# 08usb.net
KiCad netlist of a schematic drawn in Altium Designer
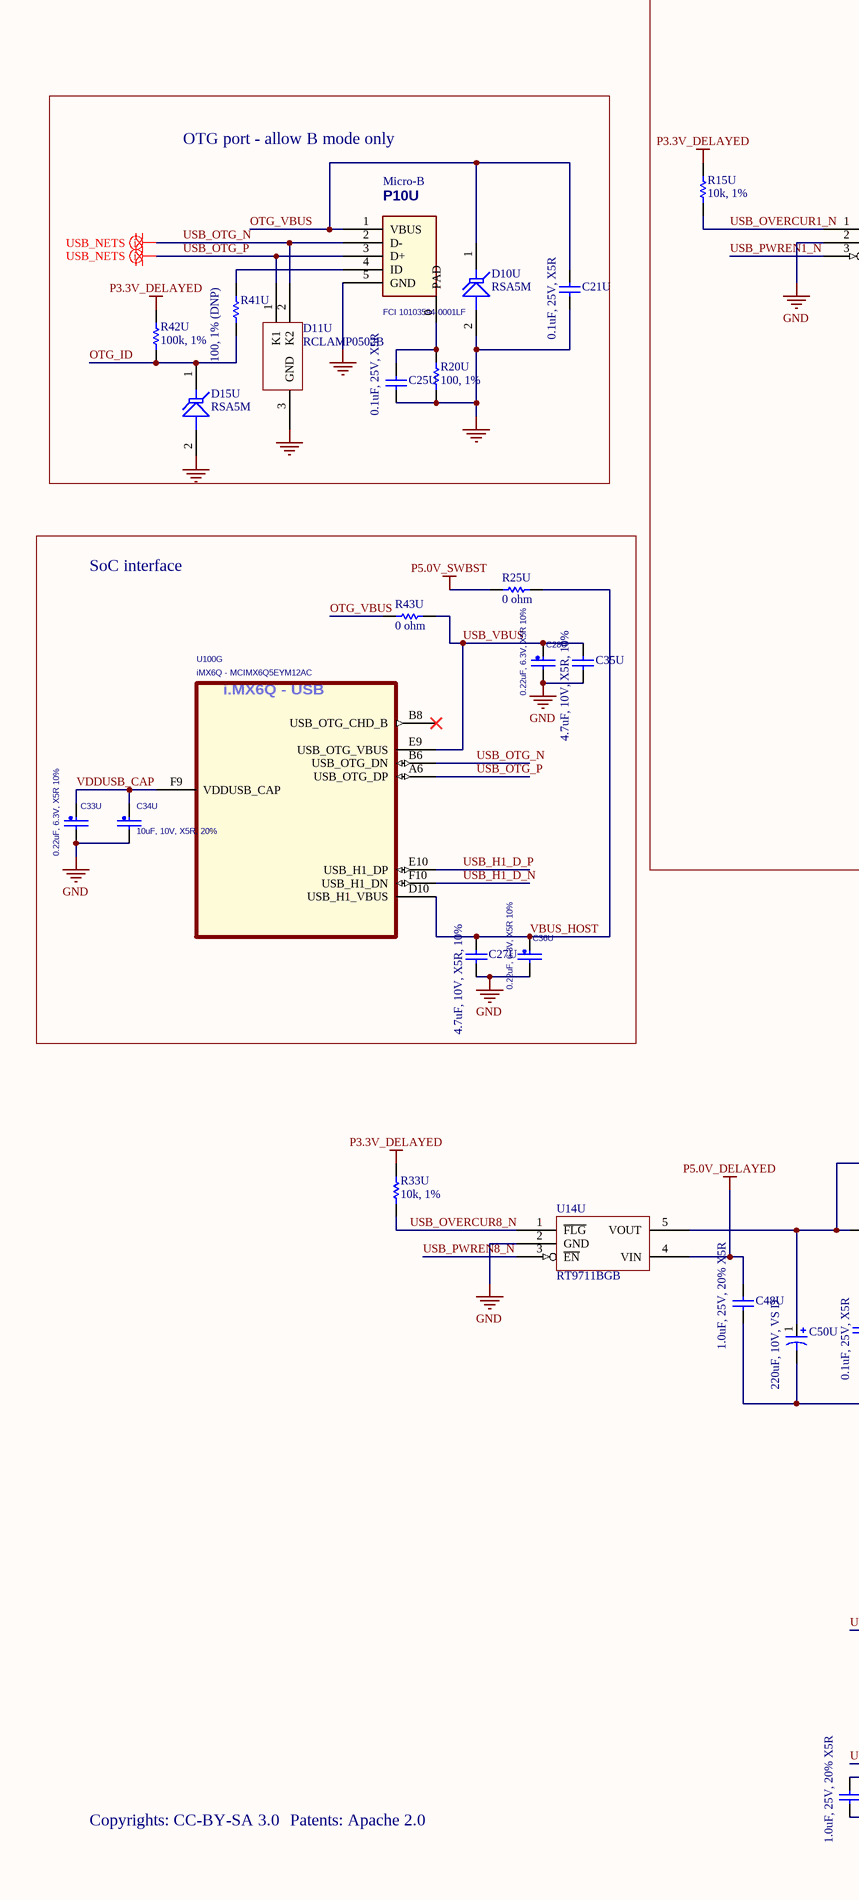
[diagram p0: 08usb.SchDoc, left]
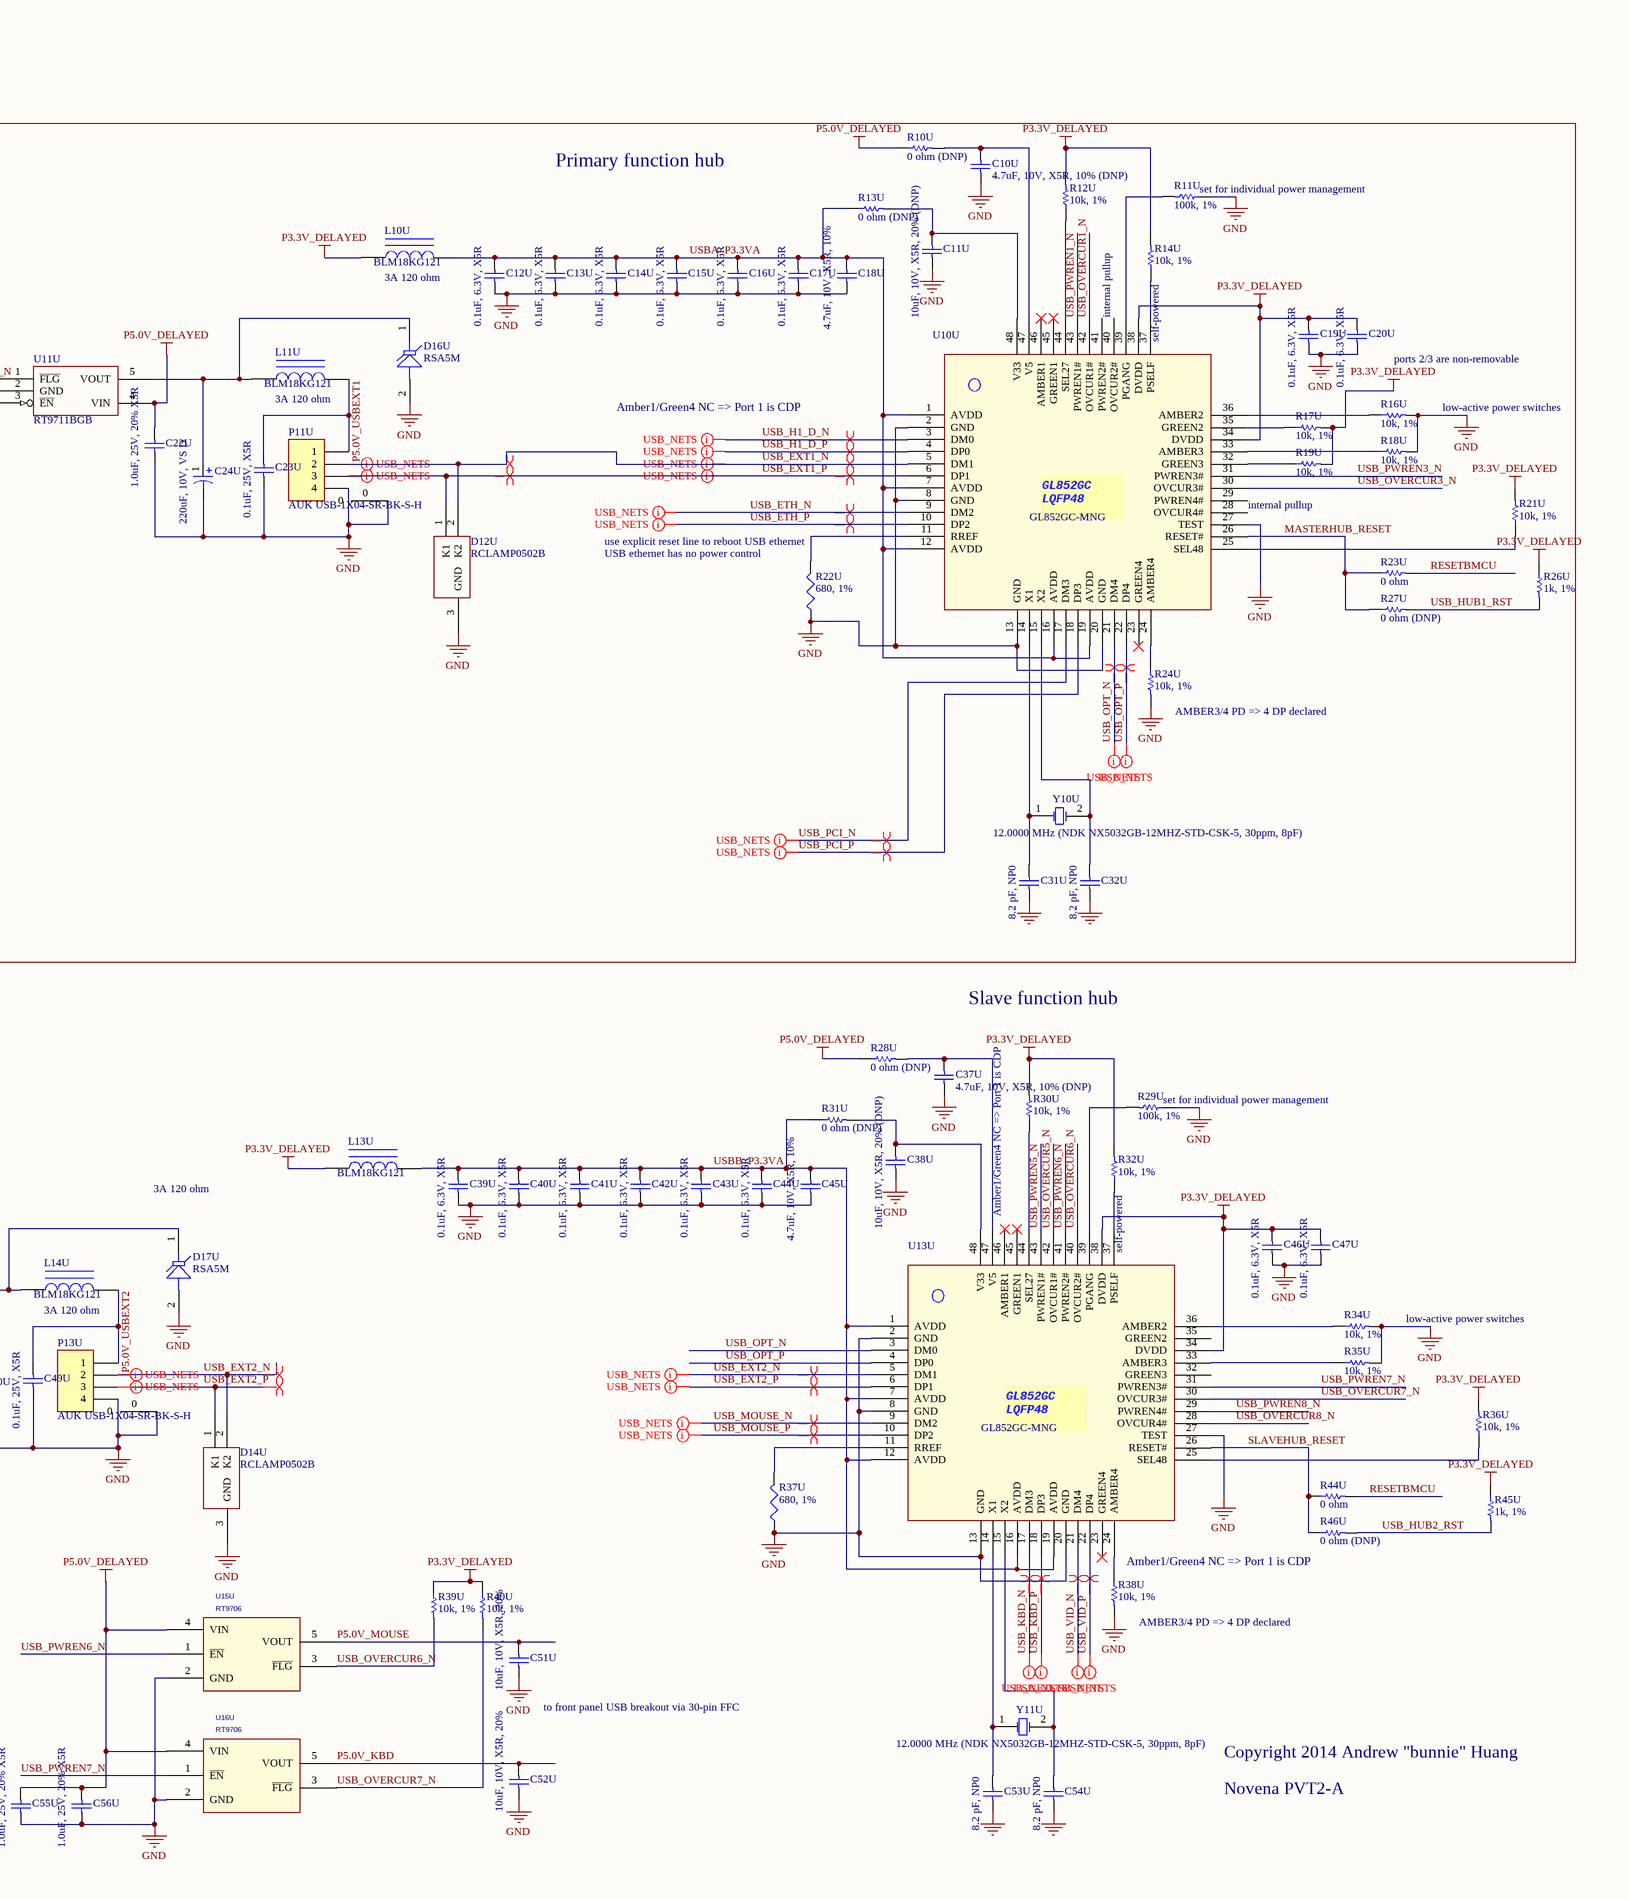
[diagram p1: 08usb.SchDoc, right]

(export (version "E")
  (design (tool "Eeschema 10.0.6"))
  (components
    (comp (ref "C10U")
      (value "4.7uF, 10V, X5R, 10% (DNP)")
      (footprint "CAPC1608N")
      (description "Capacitor (Semiconductor SIM Model)")
      (fields (field (name "PUBLISHER") "Altium Limited"))
      (libsource (lib "Miscellaneous Devices") (part "Cap Semi"))
    )
    (comp (ref "C11U")
      (value "10uF, 10V, X5R, 20% (DNP)")
      (footprint "CAPC1608N")
      (description "Capacitor (Semiconductor SIM Model)")
      (fields (field (name "PUBLISHER") "Altium Limited"))
      (libsource (lib "Miscellaneous Devices") (part "Cap Semi"))
    )
    (comp (ref "C12U")
      (value "0.1uF, 6.3V, X5R")
      (footprint "CAPC0603N_B")
      (description "Capacitor (Semiconductor SIM Model)")
      (fields (field (name "PUBLISHER") "Altium Limited"))
      (libsource (lib "Miscellaneous Devices") (part "Cap Semi"))
    )
    (comp (ref "C13U")
      (value "0.1uF, 6.3V, X5R")
      (footprint "CAPC0603N_B")
      (description "Capacitor (Semiconductor SIM Model)")
      (fields (field (name "PUBLISHER") "Altium Limited"))
      (libsource (lib "Miscellaneous Devices") (part "Cap Semi"))
    )
    (comp (ref "C14U")
      (value "0.1uF, 6.3V, X5R")
      (footprint "CAPC0603N_B")
      (description "Capacitor (Semiconductor SIM Model)")
      (fields (field (name "PUBLISHER") "Altium Limited"))
      (libsource (lib "Miscellaneous Devices") (part "Cap Semi"))
    )
    (comp (ref "C15U")
      (value "0.1uF, 6.3V, X5R")
      (footprint "CAPC0603N_B")
      (description "Capacitor (Semiconductor SIM Model)")
      (fields (field (name "PUBLISHER") "Altium Limited"))
      (libsource (lib "Miscellaneous Devices") (part "Cap Semi"))
    )
    (comp (ref "C16U")
      (value "0.1uF, 6.3V, X5R")
      (footprint "CAPC0603N_B")
      (description "Capacitor (Semiconductor SIM Model)")
      (fields (field (name "PUBLISHER") "Altium Limited"))
      (libsource (lib "Miscellaneous Devices") (part "Cap Semi"))
    )
    (comp (ref "C17U")
      (value "0.1uF, 6.3V, X5R")
      (footprint "CAPC0603N_B")
      (description "Capacitor (Semiconductor SIM Model)")
      (fields (field (name "PUBLISHER") "Altium Limited"))
      (libsource (lib "Miscellaneous Devices") (part "Cap Semi"))
    )
    (comp (ref "C18U")
      (value "4.7uF, 10V, X5R, 10%")
      (footprint "CAPC1608N")
      (description "Capacitor (Semiconductor SIM Model)")
      (fields (field (name "PUBLISHER") "Altium Limited"))
      (libsource (lib "Miscellaneous Devices") (part "Cap Semi"))
    )
    (comp (ref "C19U")
      (value "0.1uF, 6.3V, X5R")
      (footprint "CAPC0603N_B")
      (description "Capacitor (Semiconductor SIM Model)")
      (fields (field (name "PUBLISHER") "Altium Limited"))
      (libsource (lib "Miscellaneous Devices") (part "Cap Semi"))
    )
    (comp (ref "C20U")
      (value "0.1uF, 6.3V, X5R")
      (footprint "CAPC0603N_B")
      (description "Capacitor (Semiconductor SIM Model)")
      (fields (field (name "PUBLISHER") "Altium Limited"))
      (libsource (lib "Miscellaneous Devices") (part "Cap Semi"))
    )
    (comp (ref "C21U")
      (value "0.1uF, 25V, X5R")
      (footprint "CAPC1005N")
      (description "Capacitor (Semiconductor SIM Model)")
      (fields (field (name "PUBLISHER") "Altium Limited"))
      (libsource (lib "Miscellaneous Devices") (part "Cap Semi"))
    )
    (comp (ref "C22U")
      (value "1.0uF, 25V, 20% X5R")
      (footprint "CAPC1608N")
      (description "Capacitor (Semiconductor SIM Model)")
      (fields (field (name "PUBLISHER") "Altium Limited"))
      (libsource (lib "Miscellaneous Devices") (part "Cap Semi"))
    )
    (comp (ref "C23U")
      (value "0.1uF, 25V, X5R")
      (footprint "CAPC1005N")
      (description "Capacitor (Semiconductor SIM Model)")
      (fields (field (name "PUBLISHER") "Altium Limited"))
      (libsource (lib "Miscellaneous Devices") (part "Cap Semi"))
    )
    (comp (ref "C24U")
      (value "220uF, 10V, VS D")
      (footprint "6004pcb:ALCAP_D")
      (description "Polarized Capacitor (Surface Mount)")
      (fields (field (name "PUBLISHER") "Altium Limited"))
      (libsource (lib "Miscellaneous Devices") (part "Cap Pol3"))
    )
    (comp (ref "C25U")
      (value "0.1uF, 25V, X5R")
      (footprint "CAPC1005N")
      (description "Capacitor (Semiconductor SIM Model)")
      (fields (field (name "PUBLISHER") "Altium Limited"))
      (libsource (lib "Miscellaneous Devices") (part "Cap Semi"))
    )
    (comp (ref "C27U")
      (value "4.7uF, 10V, X5R, 10%")
      (footprint "CAPC1608N_HD")
      (description "Capacitor (Semiconductor SIM Model)")
      (fields (field (name "PUBLISHER") "Altium Limited"))
      (libsource (lib "Miscellaneous Devices") (part "Cap Semi"))
    )
    (comp (ref "C28U")
      (value "0.22uF, 6.3V, X5R 10%")
      (footprint "CAPC0603N_B")
      (description "CAP CER 0.22UF 6.3V 20% X5R 0201")
      (fields (field (name "TOLERANCE") "10%"))
      (libsource (lib "*") (part "CAP_NP_Dup1"))
    )
    (comp (ref "C31U")
      (value "8.2 pF, NP0")
      (footprint "CAPC1005N")
      (description "Capacitor (Semiconductor SIM Model)")
      (fields (field (name "PUBLISHER") "Altium Limited"))
      (libsource (lib "Miscellaneous Devices") (part "Cap Semi"))
    )
    (comp (ref "C32U")
      (value "8.2 pF, NP0")
      (footprint "CAPC1005N")
      (description "Capacitor (Semiconductor SIM Model)")
      (fields (field (name "PUBLISHER") "Altium Limited"))
      (libsource (lib "Miscellaneous Devices") (part "Cap Semi"))
    )
    (comp (ref "C33U")
      (value "0.22uF, 6.3V, X5R 10%")
      (footprint "CAPC0603N_B")
      (description "CAP CER 0.22UF 6.3V 20% X5R 0201")
      (fields (field (name "TOLERANCE") "20%"))
      (libsource (lib "*") (part "CAP_NP_Dup1"))
    )
    (comp (ref "C34U")
      (value "10uF, 10V, X5R, 20%")
      (footprint "CAPC1608N_HD")
      (description "CAP CER 10UF 6.3V 10% X5R 0603")
      (fields (field (name "TOLERANCE") "10%"))
      (libsource (lib "*") (part "CAP_NP_Dup1"))
    )
    (comp (ref "C35U")
      (value "4.7uF, 10V, X5R, 10%")
      (footprint "CAPC1608N_HD")
      (description "Capacitor (Semiconductor SIM Model)")
      (fields (field (name "PUBLISHER") "Altium Limited"))
      (libsource (lib "Miscellaneous Devices") (part "Cap Semi"))
    )
    (comp (ref "C36U")
      (value "0.22uF, 6.3V, X5R 10%")
      (footprint "CAPC0603N_B")
      (description "CAP CER 0.22UF 6.3V 20% X5R 0201")
      (fields (field (name "TOLERANCE") "10%"))
      (libsource (lib "*") (part "CAP_NP_Dup1"))
    )
    (comp (ref "C37U")
      (value "4.7uF, 10V, X5R, 10% (DNP)")
      (footprint "CAPC1608N")
      (description "Capacitor (Semiconductor SIM Model)")
      (fields (field (name "PUBLISHER") "Altium Limited"))
      (libsource (lib "Miscellaneous Devices") (part "Cap Semi"))
    )
    (comp (ref "C38U")
      (value "10uF, 10V, X5R, 20% (DNP)")
      (footprint "CAPC1608N")
      (description "Capacitor (Semiconductor SIM Model)")
      (fields (field (name "PUBLISHER") "Altium Limited"))
      (libsource (lib "Miscellaneous Devices") (part "Cap Semi"))
    )
    (comp (ref "C39U")
      (value "0.1uF, 6.3V, X5R")
      (footprint "CAPC0603N_B")
      (description "Capacitor (Semiconductor SIM Model)")
      (fields (field (name "PUBLISHER") "Altium Limited"))
      (libsource (lib "Miscellaneous Devices") (part "Cap Semi"))
    )
    (comp (ref "C40U")
      (value "0.1uF, 6.3V, X5R")
      (footprint "CAPC0603N_B")
      (description "Capacitor (Semiconductor SIM Model)")
      (fields (field (name "PUBLISHER") "Altium Limited"))
      (libsource (lib "Miscellaneous Devices") (part "Cap Semi"))
    )
    (comp (ref "C41U")
      (value "0.1uF, 6.3V, X5R")
      (footprint "CAPC0603N_B")
      (description "Capacitor (Semiconductor SIM Model)")
      (fields (field (name "PUBLISHER") "Altium Limited"))
      (libsource (lib "Miscellaneous Devices") (part "Cap Semi"))
    )
    (comp (ref "C42U")
      (value "0.1uF, 6.3V, X5R")
      (footprint "CAPC0603N_B")
      (description "Capacitor (Semiconductor SIM Model)")
      (fields (field (name "PUBLISHER") "Altium Limited"))
      (libsource (lib "Miscellaneous Devices") (part "Cap Semi"))
    )
    (comp (ref "C43U")
      (value "0.1uF, 6.3V, X5R")
      (footprint "CAPC0603N_B")
      (description "Capacitor (Semiconductor SIM Model)")
      (fields (field (name "PUBLISHER") "Altium Limited"))
      (libsource (lib "Miscellaneous Devices") (part "Cap Semi"))
    )
    (comp (ref "C44U")
      (value "0.1uF, 6.3V, X5R")
      (footprint "CAPC0603N_B")
      (description "Capacitor (Semiconductor SIM Model)")
      (fields (field (name "PUBLISHER") "Altium Limited"))
      (libsource (lib "Miscellaneous Devices") (part "Cap Semi"))
    )
    (comp (ref "C45U")
      (value "4.7uF, 10V, X5R, 10%")
      (footprint "CAPC1608N")
      (description "Capacitor (Semiconductor SIM Model)")
      (fields (field (name "PUBLISHER") "Altium Limited"))
      (libsource (lib "Miscellaneous Devices") (part "Cap Semi"))
    )
    (comp (ref "C46U")
      (value "0.1uF, 6.3V, X5R")
      (footprint "CAPC0603N_B")
      (description "Capacitor (Semiconductor SIM Model)")
      (fields (field (name "PUBLISHER") "Altium Limited"))
      (libsource (lib "Miscellaneous Devices") (part "Cap Semi"))
    )
    (comp (ref "C47U")
      (value "0.1uF, 6.3V, X5R")
      (footprint "CAPC0603N_B")
      (description "Capacitor (Semiconductor SIM Model)")
      (fields (field (name "PUBLISHER") "Altium Limited"))
      (libsource (lib "Miscellaneous Devices") (part "Cap Semi"))
    )
    (comp (ref "C48U")
      (value "1.0uF, 25V, 20% X5R")
      (footprint "CAPC1608N")
      (description "Capacitor (Semiconductor SIM Model)")
      (fields (field (name "PUBLISHER") "Altium Limited"))
      (libsource (lib "Miscellaneous Devices") (part "Cap Semi"))
    )
    (comp (ref "C49U")
      (value "0.1uF, 25V, X5R")
      (footprint "CAPC1005N")
      (description "Capacitor (Semiconductor SIM Model)")
      (fields (field (name "PUBLISHER") "Altium Limited"))
      (libsource (lib "Miscellaneous Devices") (part "Cap Semi"))
    )
    (comp (ref "C50U")
      (value "220uF, 10V, VS D")
      (footprint "6004pcb:ALCAP_D")
      (description "Polarized Capacitor (Surface Mount)")
      (fields (field (name "PUBLISHER") "Altium Limited"))
      (libsource (lib "Miscellaneous Devices") (part "Cap Pol3"))
    )
    (comp (ref "C51U")
      (value "10uF, 10V, X5R, 20%")
      (footprint "CAPC1608N")
      (description "Capacitor (Semiconductor SIM Model)")
      (fields (field (name "PUBLISHER") "Altium Limited"))
      (libsource (lib "Miscellaneous Devices") (part "Cap Semi"))
    )
    (comp (ref "C52U")
      (value "10uF, 10V, X5R, 20%")
      (footprint "CAPC1608N")
      (description "Capacitor (Semiconductor SIM Model)")
      (fields (field (name "PUBLISHER") "Altium Limited"))
      (libsource (lib "Miscellaneous Devices") (part "Cap Semi"))
    )
    (comp (ref "C53U")
      (value "8.2 pF, NP0")
      (footprint "CAPC1005N")
      (description "Capacitor (Semiconductor SIM Model)")
      (fields (field (name "PUBLISHER") "Altium Limited"))
      (libsource (lib "Miscellaneous Devices") (part "Cap Semi"))
    )
    (comp (ref "C54U")
      (value "8.2 pF, NP0")
      (footprint "CAPC1005N")
      (description "Capacitor (Semiconductor SIM Model)")
      (fields (field (name "PUBLISHER") "Altium Limited"))
      (libsource (lib "Miscellaneous Devices") (part "Cap Semi"))
    )
    (comp (ref "C55U")
      (value "1.0uF, 25V, 20% X5R")
      (footprint "CAPC1608N")
      (description "Capacitor (Semiconductor SIM Model)")
      (fields (field (name "PUBLISHER") "Altium Limited"))
      (libsource (lib "Miscellaneous Devices") (part "Cap Semi"))
    )
    (comp (ref "C56U")
      (value "1.0uF, 25V, 20% X5R")
      (footprint "CAPC1608N")
      (description "Capacitor (Semiconductor SIM Model)")
      (fields (field (name "PUBLISHER") "Altium Limited"))
      (libsource (lib "Miscellaneous Devices") (part "Cap Semi"))
    )
    (comp (ref "D10U")
      (value "RSA5M")
      (footprint "SOD123/X.85")
      (description "Tranzorb")
      (fields (field (name "PUBLISHER") "Altium Limited"))
      (libsource (lib "Miscellaneous Devices") (part "Tranzorb"))
    )
    (comp (ref "D11U")
      (value "RCLAMP0502B")
      (footprint "SOT-523")
      (description "2-channel ESD/CDE protection device for 5V devices")
      (libsource (lib "*") (part "RCLAMP0502B"))
    )
    (comp (ref "D12U")
      (value "RCLAMP0502B")
      (footprint "SOT-523")
      (description "2-channel ESD/CDE protection device for 5V devices")
      (libsource (lib "*") (part "RCLAMP0502B"))
    )
    (comp (ref "D14U")
      (value "RCLAMP0502B")
      (footprint "SOT-523")
      (description "2-channel ESD/CDE protection device for 5V devices")
      (libsource (lib "*") (part "RCLAMP0502B"))
    )
    (comp (ref "D15U")
      (value "RSA5M")
      (footprint "SOD123/X.85")
      (description "Tranzorb")
      (fields (field (name "PUBLISHER") "Altium Limited"))
      (libsource (lib "Miscellaneous Devices") (part "Tranzorb"))
    )
    (comp (ref "D16U")
      (value "RSA5M")
      (footprint "SOD123/X.85")
      (description "Tranzorb")
      (fields (field (name "PUBLISHER") "Altium Limited"))
      (libsource (lib "Miscellaneous Devices") (part "Tranzorb"))
    )
    (comp (ref "D17U")
      (value "RSA5M")
      (footprint "SOD123/X.85")
      (description "Tranzorb")
      (fields (field (name "PUBLISHER") "Altium Limited"))
      (libsource (lib "Miscellaneous Devices") (part "Tranzorb"))
    )
    (comp (ref "L10U")
      (value "BLM18KG121")
      (footprint "INDC1608AN")
      (description "Magnetic-Core Inductor")
      (fields (field (name "ALTIUM_VALUE") "3A 120 ohm") (field (name "PUBLISHER") "Altium Limited"))
      (libsource (lib "Miscellaneous Devices") (part "Inductor Iron"))
    )
    (comp (ref "L11U")
      (value "BLM18KG121")
      (footprint "INDC1608AN")
      (description "Magnetic-Core Inductor")
      (fields (field (name "ALTIUM_VALUE") "3A 120 ohm") (field (name "PUBLISHER") "Altium Limited"))
      (libsource (lib "Miscellaneous Devices") (part "Inductor Iron"))
    )
    (comp (ref "L13U")
      (value "BLM18KG121")
      (footprint "INDC1608AN")
      (description "Magnetic-Core Inductor")
      (fields (field (name "ALTIUM_VALUE") "3A 120 ohm") (field (name "PUBLISHER") "Altium Limited"))
      (libsource (lib "Miscellaneous Devices") (part "Inductor Iron"))
    )
    (comp (ref "L14U")
      (value "BLM18KG121")
      (footprint "INDC1608AN")
      (description "Magnetic-Core Inductor")
      (fields (field (name "ALTIUM_VALUE") "3A 120 ohm") (field (name "PUBLISHER") "Altium Limited"))
      (libsource (lib "Miscellaneous Devices") (part "Inductor Iron"))
    )
    (comp (ref "P10U")
      (value "FCI 10103594-0001LF")
      (footprint "USB_MICRO_B_SMT")
      (description "Micro USB B type connector, i.e. FCI 10103594")
      (libsource (lib "*") (part "USB_MINI-AB_1"))
    )
    (comp (ref "P11U")
      (value "AUK USB-1X04-SR-BK-S-H")
      (footprint "USB_TYPEA_TH_SINGLE")
      (description "Header, 4-Pin")
      (fields (field (name "PUBLISHER") "Altium Limited"))
      (libsource (lib "Miscellaneous Connectors") (part "Header 4"))
    )
    (comp (ref "P13U")
      (value "AUK USB-1X04-SR-BK-S-H")
      (footprint "USB_TYPEA_TH_SINGLE")
      (description "Header, 4-Pin")
      (fields (field (name "PUBLISHER") "Altium Limited"))
      (libsource (lib "Miscellaneous Connectors") (part "Header 4"))
    )
    (comp (ref "R10U")
      (value "0 ohm (DNP)")
      (footprint "RESC1005N")
      (description "Resistor")
      (fields (field (name "PUBLISHER") "Altium Limited"))
      (libsource (lib "Miscellaneous Devices") (part "Res1"))
    )
    (comp (ref "R11U")
      (value "100k, 1%")
      (footprint "RESC1005N")
      (description "Resistor")
      (fields (field (name "PUBLISHER") "Altium Limited"))
      (libsource (lib "Miscellaneous Devices") (part "Res1"))
    )
    (comp (ref "R12U")
      (value "10k, 1%")
      (footprint "RESC1005N")
      (description "Resistor")
      (fields (field (name "PUBLISHER") "Altium Limited"))
      (libsource (lib "Miscellaneous Devices") (part "Res1"))
    )
    (comp (ref "R13U")
      (value "0 ohm (DNP)")
      (footprint "RESC1005N")
      (description "Resistor")
      (fields (field (name "PUBLISHER") "Altium Limited"))
      (libsource (lib "Miscellaneous Devices") (part "Res1"))
    )
    (comp (ref "R14U")
      (value "10k, 1%")
      (footprint "RESC1005N")
      (description "Resistor")
      (fields (field (name "PUBLISHER") "Altium Limited"))
      (libsource (lib "Miscellaneous Devices") (part "Res1"))
    )
    (comp (ref "R15U")
      (value "10k, 1%")
      (footprint "RESC1005N")
      (description "Resistor")
      (fields (field (name "PUBLISHER") "Altium Limited"))
      (libsource (lib "Miscellaneous Devices") (part "Res1"))
    )
    (comp (ref "R16U")
      (value "10k, 1%")
      (footprint "RESC1005N")
      (description "Resistor")
      (fields (field (name "PUBLISHER") "Altium Limited"))
      (libsource (lib "Miscellaneous Devices") (part "Res1"))
    )
    (comp (ref "R17U")
      (value "10k, 1%")
      (footprint "RESC1005N")
      (description "Resistor")
      (fields (field (name "PUBLISHER") "Altium Limited"))
      (libsource (lib "Miscellaneous Devices") (part "Res1"))
    )
    (comp (ref "R18U")
      (value "10k, 1%")
      (footprint "RESC1005N")
      (description "Resistor")
      (fields (field (name "PUBLISHER") "Altium Limited"))
      (libsource (lib "Miscellaneous Devices") (part "Res1"))
    )
    (comp (ref "R19U")
      (value "10k, 1%")
      (footprint "RESC1005N")
      (description "Resistor")
      (fields (field (name "PUBLISHER") "Altium Limited"))
      (libsource (lib "Miscellaneous Devices") (part "Res1"))
    )
    (comp (ref "R20U")
      (value "100, 1%")
      (footprint "RESC1005N")
      (description "Resistor")
      (fields (field (name "PUBLISHER") "Altium Limited"))
      (libsource (lib "Miscellaneous Devices") (part "Res1"))
    )
    (comp (ref "R21U")
      (value "10k, 1%")
      (footprint "RESC1005N")
      (description "Resistor")
      (fields (field (name "PUBLISHER") "Altium Limited"))
      (libsource (lib "Miscellaneous Devices") (part "Res1"))
    )
    (comp (ref "R22U")
      (value "680, 1%")
      (footprint "RESC1005N")
      (description "Resistor")
      (fields (field (name "PUBLISHER") "Altium Limited"))
      (libsource (lib "Miscellaneous Devices") (part "Res3"))
    )
    (comp (ref "R23U")
      (value "0 ohm")
      (footprint "RESC1005N")
      (description "Resistor")
      (fields (field (name "PUBLISHER") "Altium Limited"))
      (libsource (lib "Miscellaneous Devices") (part "Res1"))
    )
    (comp (ref "R24U")
      (value "10k, 1%")
      (footprint "RESC1005N")
      (description "Resistor")
      (fields (field (name "PUBLISHER") "Altium Limited"))
      (libsource (lib "Miscellaneous Devices") (part "Res1"))
    )
    (comp (ref "R25U")
      (value "0 ohm")
      (footprint "RESC1005N")
      (description "Resistor")
      (fields (field (name "PUBLISHER") "Altium Limited"))
      (libsource (lib "Miscellaneous Devices") (part "Res1"))
    )
    (comp (ref "R26U")
      (value "1k, 1%")
      (footprint "RESC1005N")
      (description "Resistor")
      (fields (field (name "PUBLISHER") "Altium Limited"))
      (libsource (lib "Miscellaneous Devices") (part "Res1"))
    )
    (comp (ref "R27U")
      (value "0 ohm (DNP)")
      (footprint "RESC1005N")
      (description "Resistor")
      (fields (field (name "PUBLISHER") "Altium Limited"))
      (libsource (lib "Miscellaneous Devices") (part "Res1"))
    )
    (comp (ref "R28U")
      (value "0 ohm (DNP)")
      (footprint "RESC1005N")
      (description "Resistor")
      (fields (field (name "PUBLISHER") "Altium Limited"))
      (libsource (lib "Miscellaneous Devices") (part "Res1"))
    )
    (comp (ref "R29U")
      (value "100k, 1%")
      (footprint "RESC1005N")
      (description "Resistor")
      (fields (field (name "PUBLISHER") "Altium Limited"))
      (libsource (lib "Miscellaneous Devices") (part "Res1"))
    )
    (comp (ref "R30U")
      (value "10k, 1%")
      (footprint "RESC1005N")
      (description "Resistor")
      (fields (field (name "PUBLISHER") "Altium Limited"))
      (libsource (lib "Miscellaneous Devices") (part "Res1"))
    )
    (comp (ref "R31U")
      (value "0 ohm (DNP)")
      (footprint "RESC1005N")
      (description "Resistor")
      (fields (field (name "PUBLISHER") "Altium Limited"))
      (libsource (lib "Miscellaneous Devices") (part "Res1"))
    )
    (comp (ref "R32U")
      (value "10k, 1%")
      (footprint "RESC1005N")
      (description "Resistor")
      (fields (field (name "PUBLISHER") "Altium Limited"))
      (libsource (lib "Miscellaneous Devices") (part "Res1"))
    )
    (comp (ref "R33U")
      (value "10k, 1%")
      (footprint "RESC1005N")
      (description "Resistor")
      (fields (field (name "PUBLISHER") "Altium Limited"))
      (libsource (lib "Miscellaneous Devices") (part "Res1"))
    )
    (comp (ref "R34U")
      (value "10k, 1%")
      (footprint "RESC1005N")
      (description "Resistor")
      (fields (field (name "PUBLISHER") "Altium Limited"))
      (libsource (lib "Miscellaneous Devices") (part "Res1"))
    )
    (comp (ref "R35U")
      (value "10k, 1%")
      (footprint "RESC1005N")
      (description "Resistor")
      (fields (field (name "PUBLISHER") "Altium Limited"))
      (libsource (lib "Miscellaneous Devices") (part "Res1"))
    )
    (comp (ref "R36U")
      (value "10k, 1%")
      (footprint "RESC1005N")
      (description "Resistor")
      (fields (field (name "PUBLISHER") "Altium Limited"))
      (libsource (lib "Miscellaneous Devices") (part "Res1"))
    )
    (comp (ref "R37U")
      (value "680, 1%")
      (footprint "RESC1005N")
      (description "Resistor")
      (fields (field (name "PUBLISHER") "Altium Limited"))
      (libsource (lib "Miscellaneous Devices") (part "Res3"))
    )
    (comp (ref "R38U")
      (value "10k, 1%")
      (footprint "RESC1005N")
      (description "Resistor")
      (fields (field (name "PUBLISHER") "Altium Limited"))
      (libsource (lib "Miscellaneous Devices") (part "Res1"))
    )
    (comp (ref "R39U")
      (value "10k, 1%")
      (footprint "RESC1005N")
      (description "Resistor")
      (fields (field (name "PUBLISHER") "Altium Limited"))
      (libsource (lib "Miscellaneous Devices") (part "Res1"))
    )
    (comp (ref "R40U")
      (value "10k, 1%")
      (footprint "RESC1005N")
      (description "Resistor")
      (fields (field (name "PUBLISHER") "Altium Limited"))
      (libsource (lib "Miscellaneous Devices") (part "Res1"))
    )
    (comp (ref "R41U")
      (value "100, 1% (DNP)")
      (footprint "RESC1005N")
      (description "Resistor")
      (fields (field (name "PUBLISHER") "Altium Limited"))
      (libsource (lib "Miscellaneous Devices") (part "Res1"))
    )
    (comp (ref "R42U")
      (value "100k, 1%")
      (footprint "RESC1005N")
      (description "Resistor")
      (fields (field (name "PUBLISHER") "Altium Limited"))
      (libsource (lib "Miscellaneous Devices") (part "Res1"))
    )
    (comp (ref "R43U")
      (value "0 ohm")
      (footprint "RESC1005N")
      (description "Resistor")
      (fields (field (name "PUBLISHER") "Altium Limited"))
      (libsource (lib "Miscellaneous Devices") (part "Res1"))
    )
    (comp (ref "R44U")
      (value "0 ohm")
      (footprint "RESC1005N")
      (description "Resistor")
      (fields (field (name "PUBLISHER") "Altium Limited"))
      (libsource (lib "Miscellaneous Devices") (part "Res1"))
    )
    (comp (ref "R45U")
      (value "1k, 1%")
      (footprint "RESC1005N")
      (description "Resistor")
      (fields (field (name "PUBLISHER") "Altium Limited"))
      (libsource (lib "Miscellaneous Devices") (part "Res1"))
    )
    (comp (ref "R46U")
      (value "0 ohm (DNP)")
      (footprint "RESC1005N")
      (description "Resistor")
      (fields (field (name "PUBLISHER") "Altium Limited"))
      (libsource (lib "Miscellaneous Devices") (part "Res1"))
    )
    (comp (ref "U10U")
      (value "GL852GC-MNG")
      (description "4-port multiple-TT hub with USB charging support")
      (libsource (lib "*") (part "GLI8024-48_4"))
    )
    (comp (ref "U11U")
      (value "RT9711BGB")
      (footprint "SOT23-5AN")
      (description "1.5A high-side power switch, active low enable")
      (libsource (lib "commonsch") (part "RT9711BGB"))
    )
    (comp (ref "U13U")
      (value "GL852GC-MNG")
      (description "4-port multiple-TT hub with USB charging support")
      (libsource (lib "*") (part "GLI8024-48_4"))
    )
    (comp (ref "U14U")
      (value "RT9711BGB")
      (footprint "SOT23-5AN")
      (description "1.5A high-side power switch, active low enable")
      (libsource (lib "commonsch") (part "RT9711BGB"))
    )
    (comp (ref "U15U")
      (value "RT9706")
      (description "IC LIN SW W/FLAG 500MA 2.0-5.5V SOT23-5")
      (libsource (lib "*") (part "RT9706"))
    )
    (comp (ref "U16U")
      (value "RT9706")
      (description "IC LIN SW W/FLAG 500MA 2.0-5.5V SOT23-5")
      (libsource (lib "*") (part "RT9706"))
    )
    (comp (ref "U100")
      (value "iMX6Q - MCIMX6Q5EYM12AC")
      (description "PCIMX6Q5EVT10AC")
      (libsource (lib "*") (part "PCIMX6Q6VV1A"))
    )
    (comp (ref "Y10U")
      (value "12.0000 MHz (NDK NX5032GB-12MHZ-STD-CSK-5, 30ppm, 8pF)")
      (footprint "NDK_NX5032A")
      (description "Crystal Oscillator")
      (fields (field (name "PUBLISHER") "Altium Limited"))
      (libsource (lib "Miscellaneous Devices") (part "XTAL"))
    )
    (comp (ref "Y11U")
      (value "12.0000 MHz (NDK NX5032GB-12MHZ-STD-CSK-5, 30ppm, 8pF)")
      (footprint "NDK_NX5032A")
      (description "Crystal Oscillator")
      (fields (field (name "PUBLISHER") "Altium Limited"))
      (libsource (lib "Miscellaneous Devices") (part "XTAL"))
    )
  )
  (nets
    (net (code "1") (name "/MASTERHUB_RESET") (class "Default")
      (node (ref "R23U") (pin "1") (pinfunction "1_1") (pintype "passive"))
      (node (ref "R27U") (pin "1") (pinfunction "1_1") (pintype "passive"))
      (node (ref "U10U") (pin "26") (pinfunction "RESET#_26") (pintype "passive"))
    )
    (net (code "2") (name "/OTG_ID") (class "Default")
      (node (ref "D15U") (pin "1") (pinfunction "K_1") (pintype "passive"))
      (node (ref "R41U") (pin "1") (pinfunction "1_1") (pintype "passive"))
      (node (ref "R42U") (pin "1") (pinfunction "1_1") (pintype "passive"))
    )
    (net (code "3") (name "/OTG_VBUS") (class "Default")
      (node (ref "C21U") (pin "1") (pinfunction "1_1") (pintype "passive"))
      (node (ref "D10U") (pin "1") (pinfunction "K_1") (pintype "passive"))
      (node (ref "P10U") (pin "1") (pinfunction "VBUS_1") (pintype "passive"))
      (node (ref "R43U") (pin "2") (pinfunction "2_2") (pintype "passive"))
    )
    (net (code "4") (name "/P5.0V_KBD") (class "Default")
      (node (ref "C52U") (pin "1") (pinfunction "1_1") (pintype "passive"))
      (node (ref "U16U") (pin "5") (pinfunction "VOUT_5") (pintype "passive"))
    )
    (net (code "5") (name "/P5.0V_MOUSE") (class "Default")
      (node (ref "C51U") (pin "1") (pinfunction "1_1") (pintype "passive"))
      (node (ref "U15U") (pin "5") (pinfunction "VOUT_5") (pintype "passive"))
    )
    (net (code "6") (name "/P5.0V_USBEXT1") (class "Default")
      (node (ref "C23U") (pin "1") (pinfunction "1_1") (pintype "passive"))
      (node (ref "L11U") (pin "2") (pinfunction "2_2") (pintype "passive"))
      (node (ref "P11U") (pin "1") (pinfunction "1_1") (pintype "passive"))
    )
    (net (code "7") (name "/P5.0V_USBEXT2") (class "Default")
      (node (ref "C49U") (pin "1") (pinfunction "1_1") (pintype "passive"))
      (node (ref "L14U") (pin "2") (pinfunction "2_2") (pintype "passive"))
      (node (ref "P13U") (pin "1") (pinfunction "1_1") (pintype "passive"))
    )
    (net (code "8") (name "/RESETBMCU") (class "Default")
      (node (ref "R23U") (pin "2") (pinfunction "2_2") (pintype "passive"))
      (node (ref "R44U") (pin "2") (pinfunction "2_2") (pintype "passive"))
    )
    (net (code "9") (name "/SLAVEHUB_RESET") (class "Default")
      (node (ref "R44U") (pin "1") (pinfunction "1_1") (pintype "passive"))
      (node (ref "R46U") (pin "1") (pinfunction "1_1") (pintype "passive"))
      (node (ref "U13U") (pin "26") (pinfunction "RESET#_26") (pintype "passive"))
    )
    (net (code "10") (name "/USBA_P3.3VA") (class "Default")
      (node (ref "C12U") (pin "1") (pinfunction "1_1") (pintype "passive"))
      (node (ref "C13U") (pin "1") (pinfunction "1_1") (pintype "passive"))
      (node (ref "C14U") (pin "1") (pinfunction "1_1") (pintype "passive"))
      (node (ref "C15U") (pin "1") (pinfunction "1_1") (pintype "passive"))
      (node (ref "C16U") (pin "1") (pinfunction "1_1") (pintype "passive"))
      (node (ref "C17U") (pin "1") (pinfunction "1_1") (pintype "passive"))
      (node (ref "C18U") (pin "1") (pinfunction "1_1") (pintype "passive"))
      (node (ref "L10U") (pin "2") (pinfunction "2_2") (pintype "passive"))
      (node (ref "R13U") (pin "1") (pinfunction "1_1") (pintype "passive"))
      (node (ref "U10U") (pin "1") (pinfunction "AVDD_1") (pintype "passive"))
      (node (ref "U10U") (pin "12") (pinfunction "AVDD_12") (pintype "passive"))
      (node (ref "U10U") (pin "16") (pinfunction "AVDD_16") (pintype "passive"))
      (node (ref "U10U") (pin "19") (pinfunction "AVDD_19") (pintype "passive"))
      (node (ref "U10U") (pin "7") (pinfunction "AVDD_7") (pintype "passive"))
    )
    (net (code "11") (name "/USBB_P3.3VA") (class "Default")
      (node (ref "C39U") (pin "1") (pinfunction "1_1") (pintype "passive"))
      (node (ref "C40U") (pin "1") (pinfunction "1_1") (pintype "passive"))
      (node (ref "C41U") (pin "1") (pinfunction "1_1") (pintype "passive"))
      (node (ref "C42U") (pin "1") (pinfunction "1_1") (pintype "passive"))
      (node (ref "C43U") (pin "1") (pinfunction "1_1") (pintype "passive"))
      (node (ref "C44U") (pin "1") (pinfunction "1_1") (pintype "passive"))
      (node (ref "C45U") (pin "1") (pinfunction "1_1") (pintype "passive"))
      (node (ref "L13U") (pin "2") (pinfunction "2_2") (pintype "passive"))
      (node (ref "R31U") (pin "1") (pinfunction "1_1") (pintype "passive"))
      (node (ref "U13U") (pin "1") (pinfunction "AVDD_1") (pintype "passive"))
      (node (ref "U13U") (pin "12") (pinfunction "AVDD_12") (pintype "passive"))
      (node (ref "U13U") (pin "16") (pinfunction "AVDD_16") (pintype "passive"))
      (node (ref "U13U") (pin "19") (pinfunction "AVDD_19") (pintype "passive"))
      (node (ref "U13U") (pin "7") (pinfunction "AVDD_7") (pintype "passive"))
    )
    (net (code "12") (name "/USB_ETH_N") (class "Default")
      (node (ref "U10U") (pin "9") (pinfunction "DM2_9") (pintype "passive"))
    )
    (net (code "13") (name "/USB_ETH_P") (class "Default")
      (node (ref "U10U") (pin "10") (pinfunction "DP2_10") (pintype "passive"))
    )
    (net (code "14") (name "/USB_EXT1_N") (class "Default")
      (node (ref "D12U") (pin "2") (pinfunction "K2_2") (pintype "passive"))
      (node (ref "P11U") (pin "2") (pinfunction "2_2") (pintype "passive"))
      (node (ref "U10U") (pin "5") (pinfunction "DM1_5") (pintype "passive"))
    )
    (net (code "15") (name "/USB_EXT1_P") (class "Default")
      (node (ref "D12U") (pin "1") (pinfunction "K1_1") (pintype "passive"))
      (node (ref "P11U") (pin "3") (pinfunction "3_3") (pintype "passive"))
      (node (ref "U10U") (pin "6") (pinfunction "DP1_6") (pintype "passive"))
    )
    (net (code "16") (name "/USB_EXT2_N") (class "Default")
      (node (ref "D14U") (pin "2") (pinfunction "K2_2") (pintype "passive"))
      (node (ref "P13U") (pin "2") (pinfunction "2_2") (pintype "passive"))
      (node (ref "U13U") (pin "5") (pinfunction "DM1_5") (pintype "passive"))
    )
    (net (code "17") (name "/USB_EXT2_P") (class "Default")
      (node (ref "D14U") (pin "1") (pinfunction "K1_1") (pintype "passive"))
      (node (ref "P13U") (pin "3") (pinfunction "3_3") (pintype "passive"))
      (node (ref "U13U") (pin "6") (pinfunction "DP1_6") (pintype "passive"))
    )
    (net (code "18") (name "/USB_H1_D_N") (class "Default")
      (node (ref "U100") (pin "F10") (pinfunction "USB_H1_DN_F10") (pintype "bidirectional"))
      (node (ref "U10U") (pin "3") (pinfunction "DM0_3") (pintype "passive"))
    )
    (net (code "19") (name "/USB_H1_D_P") (class "Default")
      (node (ref "U100") (pin "E10") (pinfunction "USB_H1_DP_E10") (pintype "bidirectional"))
      (node (ref "U10U") (pin "4") (pinfunction "DP0_4") (pintype "passive"))
    )
    (net (code "20") (name "/USB_HUB1_RST") (class "Default")
      (node (ref "R26U") (pin "2") (pinfunction "2_2") (pintype "passive"))
      (node (ref "R27U") (pin "2") (pinfunction "2_2") (pintype "passive"))
    )
    (net (code "21") (name "/USB_HUB2_RST") (class "Default")
      (node (ref "R45U") (pin "2") (pinfunction "2_2") (pintype "passive"))
      (node (ref "R46U") (pin "2") (pinfunction "2_2") (pintype "passive"))
    )
    (net (code "22") (name "/USB_KBD_N") (class "Default")
      (node (ref "U13U") (pin "17") (pinfunction "DM3_17") (pintype "passive"))
    )
    (net (code "23") (name "/USB_KBD_P") (class "Default")
      (node (ref "U13U") (pin "18") (pinfunction "DP3_18") (pintype "passive"))
    )
    (net (code "24") (name "/USB_MOUSE_N") (class "Default")
      (node (ref "U13U") (pin "9") (pinfunction "DM2_9") (pintype "passive"))
    )
    (net (code "25") (name "/USB_MOUSE_P") (class "Default")
      (node (ref "U13U") (pin "10") (pinfunction "DP2_10") (pintype "passive"))
    )
    (net (code "26") (name "/USB_OPT_N") (class "Default")
      (node (ref "U10U") (pin "21") (pinfunction "DM4_21") (pintype "passive"))
      (node (ref "U13U") (pin "3") (pinfunction "DM0_3") (pintype "passive"))
    )
    (net (code "27") (name "/USB_OPT_P") (class "Default")
      (node (ref "U10U") (pin "22") (pinfunction "DP4_22") (pintype "passive"))
      (node (ref "U13U") (pin "4") (pinfunction "DP0_4") (pintype "passive"))
    )
    (net (code "28") (name "/USB_OTG_N") (class "Default")
      (node (ref "D11U") (pin "2") (pinfunction "K2_2") (pintype "passive"))
      (node (ref "P10U") (pin "2") (pinfunction "D-_2") (pintype "passive"))
      (node (ref "U100") (pin "B6") (pinfunction "USB_OTG_DN_B6") (pintype "bidirectional"))
    )
    (net (code "29") (name "/USB_OTG_P") (class "Default")
      (node (ref "D11U") (pin "1") (pinfunction "K1_1") (pintype "passive"))
      (node (ref "P10U") (pin "3") (pinfunction "D+_3") (pintype "passive"))
      (node (ref "U100") (pin "A6") (pinfunction "USB_OTG_DP_A6") (pintype "bidirectional"))
    )
    (net (code "30") (name "/USB_OVERCUR1_N") (class "Default")
      (node (ref "R15U") (pin "1") (pinfunction "1_1") (pintype "passive"))
      (node (ref "U10U") (pin "42") (pinfunction "OVCUR1#_42") (pintype "passive"))
      (node (ref "U11U") (pin "1") (pinfunction "~{FLG}_1") (pintype "open_collector"))
    )
    (net (code "31") (name "/USB_OVERCUR3_N") (class "Default")
      (node (ref "U10U") (pin "30") (pinfunction "OVCUR3#_30") (pintype "passive"))
    )
    (net (code "32") (name "/USB_OVERCUR5_N") (class "Default")
      (node (ref "U13U") (pin "42") (pinfunction "OVCUR1#_42") (pintype "passive"))
    )
    (net (code "33") (name "/USB_OVERCUR6_N") (class "Default")
      (node (ref "R39U") (pin "2") (pinfunction "2_2") (pintype "passive"))
      (node (ref "U13U") (pin "40") (pinfunction "OVCUR2#_40") (pintype "passive"))
      (node (ref "U15U") (pin "3") (pinfunction "~{FLG}_3") (pintype "passive"))
    )
    (net (code "34") (name "/USB_OVERCUR7_N") (class "Default")
      (node (ref "R40U") (pin "2") (pinfunction "2_2") (pintype "passive"))
      (node (ref "U13U") (pin "30") (pinfunction "OVCUR3#_30") (pintype "passive"))
      (node (ref "U16U") (pin "3") (pinfunction "~{FLG}_3") (pintype "passive"))
    )
    (net (code "35") (name "/USB_OVERCUR8_N") (class "Default")
      (node (ref "R33U") (pin "1") (pinfunction "1_1") (pintype "passive"))
      (node (ref "U13U") (pin "28") (pinfunction "OVCUR4#_28") (pintype "passive"))
      (node (ref "U14U") (pin "1") (pinfunction "~{FLG}_1") (pintype "open_collector"))
    )
    (net (code "36") (name "/USB_PCI_N") (class "Default")
      (node (ref "U10U") (pin "17") (pinfunction "DM3_17") (pintype "passive"))
    )
    (net (code "37") (name "/USB_PCI_P") (class "Default")
      (node (ref "U10U") (pin "18") (pinfunction "DP3_18") (pintype "passive"))
    )
    (net (code "38") (name "/USB_PWREN1_N") (class "Default")
      (node (ref "U10U") (pin "43") (pinfunction "PWREN1#_43") (pintype "passive"))
      (node (ref "U11U") (pin "3") (pinfunction "~{EN}_3") (pintype "input"))
    )
    (net (code "39") (name "/USB_PWREN3_N") (class "Default")
      (node (ref "U10U") (pin "31") (pinfunction "PWREN3#_31") (pintype "passive"))
    )
    (net (code "40") (name "/USB_PWREN5_N") (class "Default")
      (node (ref "U13U") (pin "43") (pinfunction "PWREN1#_43") (pintype "passive"))
    )
    (net (code "41") (name "/USB_PWREN6_N") (class "Default")
      (node (ref "U13U") (pin "41") (pinfunction "PWREN2#_41") (pintype "passive"))
      (node (ref "U15U") (pin "1") (pinfunction "~{EN}_1") (pintype "passive"))
    )
    (net (code "42") (name "/USB_PWREN7_N") (class "Default")
      (node (ref "U13U") (pin "31") (pinfunction "PWREN3#_31") (pintype "passive"))
      (node (ref "U16U") (pin "1") (pinfunction "~{EN}_1") (pintype "passive"))
    )
    (net (code "43") (name "/USB_PWREN8_N") (class "Default")
      (node (ref "U13U") (pin "29") (pinfunction "PWREN4#_29") (pintype "passive"))
      (node (ref "U14U") (pin "3") (pinfunction "~{EN}_3") (pintype "input"))
    )
    (net (code "44") (name "/USB_VBUS") (class "Default")
      (node (ref "C28U") (pin "1") (pinfunction "1_1") (pintype "passive"))
      (node (ref "C35U") (pin "1") (pinfunction "1_1") (pintype "passive"))
      (node (ref "R43U") (pin "1") (pinfunction "1_1") (pintype "passive"))
      (node (ref "U100") (pin "E9") (pinfunction "USB_OTG_VBUS_E9") (pintype "power_in"))
    )
    (net (code "45") (name "/USB_VID_N") (class "Default")
      (node (ref "U13U") (pin "21") (pinfunction "DM4_21") (pintype "passive"))
    )
    (net (code "46") (name "/USB_VID_P") (class "Default")
      (node (ref "U13U") (pin "22") (pinfunction "DP4_22") (pintype "passive"))
    )
    (net (code "47") (name "/VBUS_HOST") (class "Default")
      (node (ref "C27U") (pin "1") (pinfunction "1_1") (pintype "passive"))
      (node (ref "C36U") (pin "1") (pinfunction "1_1") (pintype "passive"))
      (node (ref "R25U") (pin "1") (pinfunction "1_1") (pintype "passive"))
      (node (ref "U100") (pin "D10") (pinfunction "USB_H1_VBUS_D10") (pintype "power_in"))
    )
    (net (code "48") (name "/VDDUSB_CAP") (class "Default")
      (node (ref "C33U") (pin "1") (pinfunction "1_1") (pintype "passive"))
      (node (ref "C34U") (pin "1") (pinfunction "1_1") (pintype "passive"))
      (node (ref "U100") (pin "F9") (pinfunction "VDDUSB_CAP_F9") (pintype "power_in"))
    )
    (net (code "49") (name "GND") (class "Default")
      (node (ref "C10U") (pin "2") (pinfunction "2_2") (pintype "passive"))
      (node (ref "C11U") (pin "2") (pinfunction "2_2") (pintype "passive"))
      (node (ref "C12U") (pin "2") (pinfunction "2_2") (pintype "passive"))
      (node (ref "C13U") (pin "2") (pinfunction "2_2") (pintype "passive"))
      (node (ref "C14U") (pin "2") (pinfunction "2_2") (pintype "passive"))
      (node (ref "C15U") (pin "2") (pinfunction "2_2") (pintype "passive"))
      (node (ref "C16U") (pin "2") (pinfunction "2_2") (pintype "passive"))
      (node (ref "C17U") (pin "2") (pinfunction "2_2") (pintype "passive"))
      (node (ref "C18U") (pin "2") (pinfunction "2_2") (pintype "passive"))
      (node (ref "C19U") (pin "2") (pinfunction "2_2") (pintype "passive"))
      (node (ref "C20U") (pin "2") (pinfunction "2_2") (pintype "passive"))
      (node (ref "C21U") (pin "2") (pinfunction "2_2") (pintype "passive"))
      (node (ref "C22U") (pin "2") (pinfunction "2_2") (pintype "passive"))
      (node (ref "C23U") (pin "2") (pinfunction "2_2") (pintype "passive"))
      (node (ref "C24U") (pin "2") (pinfunction "2_2") (pintype "passive"))
      (node (ref "C25U") (pin "2") (pinfunction "2_2") (pintype "passive"))
      (node (ref "C27U") (pin "2") (pinfunction "2_2") (pintype "passive"))
      (node (ref "C28U") (pin "2") (pinfunction "2_2") (pintype "passive"))
      (node (ref "C31U") (pin "2") (pinfunction "2_2") (pintype "passive"))
      (node (ref "C32U") (pin "2") (pinfunction "2_2") (pintype "passive"))
      (node (ref "C33U") (pin "2") (pinfunction "2_2") (pintype "passive"))
      (node (ref "C34U") (pin "2") (pinfunction "2_2") (pintype "passive"))
      (node (ref "C35U") (pin "2") (pinfunction "2_2") (pintype "passive"))
      (node (ref "C36U") (pin "2") (pinfunction "2_2") (pintype "passive"))
      (node (ref "C37U") (pin "2") (pinfunction "2_2") (pintype "passive"))
      (node (ref "C38U") (pin "2") (pinfunction "2_2") (pintype "passive"))
      (node (ref "C39U") (pin "2") (pinfunction "2_2") (pintype "passive"))
      (node (ref "C40U") (pin "2") (pinfunction "2_2") (pintype "passive"))
      (node (ref "C41U") (pin "2") (pinfunction "2_2") (pintype "passive"))
      (node (ref "C42U") (pin "2") (pinfunction "2_2") (pintype "passive"))
      (node (ref "C43U") (pin "2") (pinfunction "2_2") (pintype "passive"))
      (node (ref "C44U") (pin "2") (pinfunction "2_2") (pintype "passive"))
      (node (ref "C45U") (pin "2") (pinfunction "2_2") (pintype "passive"))
      (node (ref "C46U") (pin "2") (pinfunction "2_2") (pintype "passive"))
      (node (ref "C47U") (pin "2") (pinfunction "2_2") (pintype "passive"))
      (node (ref "C48U") (pin "2") (pinfunction "2_2") (pintype "passive"))
      (node (ref "C49U") (pin "2") (pinfunction "2_2") (pintype "passive"))
      (node (ref "C50U") (pin "2") (pinfunction "2_2") (pintype "passive"))
      (node (ref "C51U") (pin "2") (pinfunction "2_2") (pintype "passive"))
      (node (ref "C52U") (pin "2") (pinfunction "2_2") (pintype "passive"))
      (node (ref "C53U") (pin "2") (pinfunction "2_2") (pintype "passive"))
      (node (ref "C54U") (pin "2") (pinfunction "2_2") (pintype "passive"))
      (node (ref "C55U") (pin "2") (pinfunction "2_2") (pintype "passive"))
      (node (ref "C56U") (pin "2") (pinfunction "2_2") (pintype "passive"))
      (node (ref "D10U") (pin "2") (pinfunction "A_2") (pintype "passive"))
      (node (ref "D11U") (pin "3") (pinfunction "GND_3") (pintype "passive"))
      (node (ref "D12U") (pin "3") (pinfunction "GND_3") (pintype "passive"))
      (node (ref "D14U") (pin "3") (pinfunction "GND_3") (pintype "passive"))
      (node (ref "D15U") (pin "2") (pinfunction "A_2") (pintype "passive"))
      (node (ref "D16U") (pin "2") (pinfunction "A_2") (pintype "passive"))
      (node (ref "D17U") (pin "2") (pinfunction "A_2") (pintype "passive"))
      (node (ref "P10U") (pin "5") (pinfunction "GND_5") (pintype "passive"))
      (node (ref "P11U") (pin "0") (pinfunction "0_0") (pintype "passive"))
      (node (ref "P11U") (pin "4") (pinfunction "4_4") (pintype "passive"))
      (node (ref "P13U") (pin "0") (pinfunction "0_0") (pintype "passive"))
      (node (ref "P13U") (pin "4") (pinfunction "4_4") (pintype "passive"))
      (node (ref "R11U") (pin "1") (pinfunction "1_1") (pintype "passive"))
      (node (ref "R16U") (pin "2") (pinfunction "2_2") (pintype "passive"))
      (node (ref "R18U") (pin "2") (pinfunction "2_2") (pintype "passive"))
      (node (ref "R20U") (pin "2") (pinfunction "2_2") (pintype "passive"))
      (node (ref "R22U") (pin "1") (pinfunction "1_1") (pintype "passive"))
      (node (ref "R24U") (pin "2") (pinfunction "2_2") (pintype "passive"))
      (node (ref "R29U") (pin "1") (pinfunction "1_1") (pintype "passive"))
      (node (ref "R34U") (pin "2") (pinfunction "2_2") (pintype "passive"))
      (node (ref "R35U") (pin "2") (pinfunction "2_2") (pintype "passive"))
      (node (ref "R37U") (pin "1") (pinfunction "1_1") (pintype "passive"))
      (node (ref "R38U") (pin "2") (pinfunction "2_2") (pintype "passive"))
      (node (ref "U10U") (pin "13") (pinfunction "GND_13") (pintype "passive"))
      (node (ref "U10U") (pin "2") (pinfunction "GND_2") (pintype "passive"))
      (node (ref "U10U") (pin "20") (pinfunction "GND_20") (pintype "passive"))
      (node (ref "U10U") (pin "27") (pinfunction "TEST_27") (pintype "passive"))
      (node (ref "U10U") (pin "8") (pinfunction "GND_8") (pintype "passive"))
      (node (ref "U11U") (pin "2") (pinfunction "GND_2") (pintype "power_in"))
      (node (ref "U13U") (pin "13") (pinfunction "GND_13") (pintype "passive"))
      (node (ref "U13U") (pin "2") (pinfunction "GND_2") (pintype "passive"))
      (node (ref "U13U") (pin "20") (pinfunction "GND_20") (pintype "passive"))
      (node (ref "U13U") (pin "27") (pinfunction "TEST_27") (pintype "passive"))
      (node (ref "U13U") (pin "8") (pinfunction "GND_8") (pintype "passive"))
      (node (ref "U14U") (pin "2") (pinfunction "GND_2") (pintype "power_in"))
      (node (ref "U15U") (pin "2") (pinfunction "GND_2") (pintype "power_in"))
      (node (ref "U16U") (pin "2") (pinfunction "GND_2") (pintype "power_in"))
    )
    (net (code "50") (name "Net-(D16U-K)") (class "Default")
      (node (ref "C24U") (pin "1") (pinfunction "1_1") (pintype "passive"))
      (node (ref "D16U") (pin "1") (pinfunction "K_1") (pintype "passive"))
      (node (ref "L11U") (pin "1") (pinfunction "1_1") (pintype "passive"))
      (node (ref "U11U") (pin "5") (pinfunction "VOUT_5") (pintype "power_in"))
    )
    (net (code "51") (name "Net-(D17U-K)") (class "Default")
      (node (ref "C50U") (pin "1") (pinfunction "1_1") (pintype "passive"))
      (node (ref "D17U") (pin "1") (pinfunction "K_1") (pintype "passive"))
      (node (ref "L14U") (pin "1") (pinfunction "1_1") (pintype "passive"))
      (node (ref "U14U") (pin "5") (pinfunction "VOUT_5") (pintype "power_in"))
    )
    (net (code "52") (name "Net-(P10U-ID)") (class "Default")
      (node (ref "P10U") (pin "4") (pinfunction "ID_4") (pintype "passive"))
      (node (ref "R41U") (pin "2") (pinfunction "2_2") (pintype "passive"))
    )
    (net (code "53") (name "Net-(P10U-PAD)") (class "Default")
      (node (ref "C25U") (pin "1") (pinfunction "1_1") (pintype "passive"))
      (node (ref "P10U") (pin "0") (pinfunction "PAD_0") (pintype "passive"))
      (node (ref "R20U") (pin "1") (pinfunction "1_1") (pintype "passive"))
    )
    (net (code "54") (name "Net-(U10U-AMBER2)") (class "Default")
      (node (ref "R16U") (pin "1") (pinfunction "1_1") (pintype "passive"))
      (node (ref "U10U") (pin "36") (pinfunction "AMBER2_36") (pintype "passive"))
    )
    (net (code "55") (name "Net-(U10U-AMBER3)") (class "Default")
      (node (ref "R18U") (pin "1") (pinfunction "1_1") (pintype "passive"))
      (node (ref "U10U") (pin "33") (pinfunction "AMBER3_33") (pintype "passive"))
    )
    (net (code "56") (name "Net-(U10U-AMBER4)") (class "Default")
      (node (ref "R24U") (pin "1") (pinfunction "1_1") (pintype "passive"))
      (node (ref "U10U") (pin "24") (pinfunction "AMBER4_24") (pintype "passive"))
    )
    (net (code "57") (name "Net-(U10U-GREEN2)") (class "Default")
      (node (ref "R17U") (pin "1") (pinfunction "1_1") (pintype "passive"))
      (node (ref "U10U") (pin "35") (pinfunction "GREEN2_35") (pintype "passive"))
    )
    (net (code "58") (name "Net-(U10U-GREEN3)") (class "Default")
      (node (ref "R19U") (pin "1") (pinfunction "1_1") (pintype "passive"))
      (node (ref "U10U") (pin "32") (pinfunction "GREEN3_32") (pintype "passive"))
    )
    (net (code "59") (name "Net-(U10U-PGANG)") (class "Default")
      (node (ref "R11U") (pin "2") (pinfunction "2_2") (pintype "passive"))
      (node (ref "U10U") (pin "39") (pinfunction "PGANG_39") (pintype "passive"))
    )
    (net (code "60") (name "Net-(U10U-PSELF)") (class "Default")
      (node (ref "R14U") (pin "1") (pinfunction "1_1") (pintype "passive"))
      (node (ref "U10U") (pin "37") (pinfunction "PSELF_37") (pintype "passive"))
    )
    (net (code "61") (name "Net-(U10U-RREF)") (class "Default")
      (node (ref "R22U") (pin "2") (pinfunction "2_2") (pintype "passive"))
      (node (ref "U10U") (pin "11") (pinfunction "RREF_11") (pintype "passive"))
    )
    (net (code "62") (name "Net-(U10U-SEL27)") (class "Default")
      (node (ref "R12U") (pin "1") (pinfunction "1_1") (pintype "passive"))
      (node (ref "U10U") (pin "44") (pinfunction "SEL27_44") (pintype "passive"))
    )
    (net (code "63") (name "Net-(U10U-SEL48)") (class "Default")
      (node (ref "R21U") (pin "1") (pinfunction "1_1") (pintype "passive"))
      (node (ref "U10U") (pin "25") (pinfunction "SEL48_25") (pintype "passive"))
    )
    (net (code "64") (name "Net-(U10U-V5)") (class "Default")
      (node (ref "C10U") (pin "1") (pinfunction "1_1") (pintype "passive"))
      (node (ref "R10U") (pin "2") (pinfunction "2_2") (pintype "passive"))
      (node (ref "U10U") (pin "47") (pinfunction "V5_47") (pintype "passive"))
    )
    (net (code "65") (name "Net-(U10U-V33)") (class "Default")
      (node (ref "C11U") (pin "1") (pinfunction "1_1") (pintype "passive"))
      (node (ref "R13U") (pin "2") (pinfunction "2_2") (pintype "passive"))
      (node (ref "U10U") (pin "48") (pinfunction "V33_48") (pintype "passive"))
    )
    (net (code "66") (name "Net-(U10U-X1)") (class "Default")
      (node (ref "C31U") (pin "1") (pinfunction "1_1") (pintype "passive"))
      (node (ref "U10U") (pin "14") (pinfunction "X1_14") (pintype "passive"))
      (node (ref "Y10U") (pin "1") (pinfunction "OSC1_1") (pintype "passive"))
    )
    (net (code "67") (name "Net-(U10U-X2)") (class "Default")
      (node (ref "C32U") (pin "1") (pinfunction "1_1") (pintype "passive"))
      (node (ref "U10U") (pin "15") (pinfunction "X2_15") (pintype "passive"))
      (node (ref "Y10U") (pin "2") (pinfunction "OSC2_2") (pintype "passive"))
    )
    (net (code "68") (name "Net-(U13U-AMBER2)") (class "Default")
      (node (ref "R34U") (pin "1") (pinfunction "1_1") (pintype "passive"))
      (node (ref "U13U") (pin "36") (pinfunction "AMBER2_36") (pintype "passive"))
    )
    (net (code "69") (name "Net-(U13U-AMBER3)") (class "Default")
      (node (ref "R35U") (pin "1") (pinfunction "1_1") (pintype "passive"))
      (node (ref "U13U") (pin "33") (pinfunction "AMBER3_33") (pintype "passive"))
    )
    (net (code "70") (name "Net-(U13U-AMBER4)") (class "Default")
      (node (ref "R38U") (pin "1") (pinfunction "1_1") (pintype "passive"))
      (node (ref "U13U") (pin "24") (pinfunction "AMBER4_24") (pintype "passive"))
    )
    (net (code "71") (name "Net-(U13U-PGANG)") (class "Default")
      (node (ref "R29U") (pin "2") (pinfunction "2_2") (pintype "passive"))
      (node (ref "U13U") (pin "39") (pinfunction "PGANG_39") (pintype "passive"))
    )
    (net (code "72") (name "Net-(U13U-PSELF)") (class "Default")
      (node (ref "R32U") (pin "1") (pinfunction "1_1") (pintype "passive"))
      (node (ref "U13U") (pin "37") (pinfunction "PSELF_37") (pintype "passive"))
    )
    (net (code "73") (name "Net-(U13U-RREF)") (class "Default")
      (node (ref "R37U") (pin "2") (pinfunction "2_2") (pintype "passive"))
      (node (ref "U13U") (pin "11") (pinfunction "RREF_11") (pintype "passive"))
    )
    (net (code "74") (name "Net-(U13U-SEL27)") (class "Default")
      (node (ref "R30U") (pin "1") (pinfunction "1_1") (pintype "passive"))
      (node (ref "U13U") (pin "44") (pinfunction "SEL27_44") (pintype "passive"))
    )
    (net (code "75") (name "Net-(U13U-SEL48)") (class "Default")
      (node (ref "R36U") (pin "1") (pinfunction "1_1") (pintype "passive"))
      (node (ref "U13U") (pin "25") (pinfunction "SEL48_25") (pintype "passive"))
    )
    (net (code "76") (name "Net-(U13U-V5)") (class "Default")
      (node (ref "C37U") (pin "1") (pinfunction "1_1") (pintype "passive"))
      (node (ref "R28U") (pin "2") (pinfunction "2_2") (pintype "passive"))
      (node (ref "U13U") (pin "47") (pinfunction "V5_47") (pintype "passive"))
    )
    (net (code "77") (name "Net-(U13U-V33)") (class "Default")
      (node (ref "C38U") (pin "1") (pinfunction "1_1") (pintype "passive"))
      (node (ref "R31U") (pin "2") (pinfunction "2_2") (pintype "passive"))
      (node (ref "U13U") (pin "48") (pinfunction "V33_48") (pintype "passive"))
    )
    (net (code "78") (name "Net-(U13U-X1)") (class "Default")
      (node (ref "C53U") (pin "1") (pinfunction "1_1") (pintype "passive"))
      (node (ref "U13U") (pin "14") (pinfunction "X1_14") (pintype "passive"))
      (node (ref "Y11U") (pin "1") (pinfunction "OSC1_1") (pintype "passive"))
    )
    (net (code "79") (name "Net-(U13U-X2)") (class "Default")
      (node (ref "C54U") (pin "1") (pinfunction "1_1") (pintype "passive"))
      (node (ref "U13U") (pin "15") (pinfunction "X2_15") (pintype "passive"))
      (node (ref "Y11U") (pin "2") (pinfunction "OSC2_2") (pintype "passive"))
    )
    (net (code "80") (name "P3.3V_DELAYED") (class "Default")
      (node (ref "C19U") (pin "1") (pinfunction "1_1") (pintype "passive"))
      (node (ref "C20U") (pin "1") (pinfunction "1_1") (pintype "passive"))
      (node (ref "C46U") (pin "1") (pinfunction "1_1") (pintype "passive"))
      (node (ref "C47U") (pin "1") (pinfunction "1_1") (pintype "passive"))
      (node (ref "L10U") (pin "1") (pinfunction "1_1") (pintype "passive"))
      (node (ref "L13U") (pin "1") (pinfunction "1_1") (pintype "passive"))
      (node (ref "R12U") (pin "2") (pinfunction "2_2") (pintype "passive"))
      (node (ref "R14U") (pin "2") (pinfunction "2_2") (pintype "passive"))
      (node (ref "R15U") (pin "2") (pinfunction "2_2") (pintype "passive"))
      (node (ref "R17U") (pin "2") (pinfunction "2_2") (pintype "passive"))
      (node (ref "R19U") (pin "2") (pinfunction "2_2") (pintype "passive"))
      (node (ref "R21U") (pin "2") (pinfunction "2_2") (pintype "passive"))
      (node (ref "R26U") (pin "1") (pinfunction "1_1") (pintype "passive"))
      (node (ref "R30U") (pin "2") (pinfunction "2_2") (pintype "passive"))
      (node (ref "R32U") (pin "2") (pinfunction "2_2") (pintype "passive"))
      (node (ref "R33U") (pin "2") (pinfunction "2_2") (pintype "passive"))
      (node (ref "R36U") (pin "2") (pinfunction "2_2") (pintype "passive"))
      (node (ref "R39U") (pin "1") (pinfunction "1_1") (pintype "passive"))
      (node (ref "R40U") (pin "1") (pinfunction "1_1") (pintype "passive"))
      (node (ref "R42U") (pin "2") (pinfunction "2_2") (pintype "passive"))
      (node (ref "R45U") (pin "1") (pinfunction "1_1") (pintype "passive"))
      (node (ref "U10U") (pin "34") (pinfunction "DVDD_34") (pintype "passive"))
      (node (ref "U10U") (pin "38") (pinfunction "DVDD_38") (pintype "passive"))
      (node (ref "U13U") (pin "34") (pinfunction "DVDD_34") (pintype "passive"))
      (node (ref "U13U") (pin "38") (pinfunction "DVDD_38") (pintype "passive"))
    )
    (net (code "81") (name "P5.0V_DELAYED") (class "Default")
      (node (ref "C22U") (pin "1") (pinfunction "1_1") (pintype "passive"))
      (node (ref "C48U") (pin "1") (pinfunction "1_1") (pintype "passive"))
      (node (ref "C55U") (pin "1") (pinfunction "1_1") (pintype "passive"))
      (node (ref "C56U") (pin "1") (pinfunction "1_1") (pintype "passive"))
      (node (ref "R10U") (pin "1") (pinfunction "1_1") (pintype "passive"))
      (node (ref "R28U") (pin "1") (pinfunction "1_1") (pintype "passive"))
      (node (ref "U11U") (pin "4") (pinfunction "VIN_4") (pintype "power_in"))
      (node (ref "U14U") (pin "4") (pinfunction "VIN_4") (pintype "power_in"))
      (node (ref "U15U") (pin "4") (pinfunction "VIN_4") (pintype "passive"))
      (node (ref "U16U") (pin "4") (pinfunction "VIN_4") (pintype "passive"))
    )
    (net (code "82") (name "P5.0V_SWBST") (class "Default")
      (node (ref "R25U") (pin "2") (pinfunction "2_2") (pintype "passive"))
    )
    (net (code "83") (name "unconnected-(U10U-AMBER1-Pad46)") (class "Default")
      (node (ref "U10U") (pin "46") (pinfunction "AMBER1_46") (pintype "passive+no_connect"))
    )
    (net (code "84") (name "unconnected-(U10U-GREEN1-Pad45)") (class "Default")
      (node (ref "U10U") (pin "45") (pinfunction "GREEN1_45") (pintype "passive+no_connect"))
    )
    (net (code "85") (name "unconnected-(U10U-GREEN4-Pad23)") (class "Default")
      (node (ref "U10U") (pin "23") (pinfunction "GREEN4_23") (pintype "passive+no_connect"))
    )
    (net (code "86") (name "unconnected-(U10U-OVCUR2#-Pad40)") (class "Default")
      (node (ref "U10U") (pin "40") (pinfunction "OVCUR2#_40") (pintype "passive"))
    )
    (net (code "87") (name "unconnected-(U10U-OVCUR4#-Pad28)") (class "Default")
      (node (ref "U10U") (pin "28") (pinfunction "OVCUR4#_28") (pintype "passive"))
    )
    (net (code "88") (name "unconnected-(U10U-PWREN2#-Pad41)") (class "Default")
      (node (ref "U10U") (pin "41") (pinfunction "PWREN2#_41") (pintype "passive"))
    )
    (net (code "89") (name "unconnected-(U10U-PWREN4#-Pad29)") (class "Default")
      (node (ref "U10U") (pin "29") (pinfunction "PWREN4#_29") (pintype "passive"))
    )
    (net (code "90") (name "unconnected-(U13U-AMBER1-Pad46)") (class "Default")
      (node (ref "U13U") (pin "46") (pinfunction "AMBER1_46") (pintype "passive+no_connect"))
    )
    (net (code "91") (name "unconnected-(U13U-GREEN1-Pad45)") (class "Default")
      (node (ref "U13U") (pin "45") (pinfunction "GREEN1_45") (pintype "passive+no_connect"))
    )
    (net (code "92") (name "unconnected-(U13U-GREEN2-Pad35)") (class "Default")
      (node (ref "U13U") (pin "35") (pinfunction "GREEN2_35") (pintype "passive"))
    )
    (net (code "93") (name "unconnected-(U13U-GREEN3-Pad32)") (class "Default")
      (node (ref "U13U") (pin "32") (pinfunction "GREEN3_32") (pintype "passive"))
    )
    (net (code "94") (name "unconnected-(U13U-GREEN4-Pad23)") (class "Default")
      (node (ref "U13U") (pin "23") (pinfunction "GREEN4_23") (pintype "passive+no_connect"))
    )
    (net (code "95") (name "unconnected-(U100G-USB_OTG_CHD_B-PadB8)") (class "Default")
      (node (ref "U100") (pin "B8") (pinfunction "USB_OTG_CHD_B_B8") (pintype "output+no_connect"))
    )
  )
)
